# Cargador_RasPi3HAT_CamSlot_v1_2.net
KiCad netlist of a schematic drawn in EAGLE
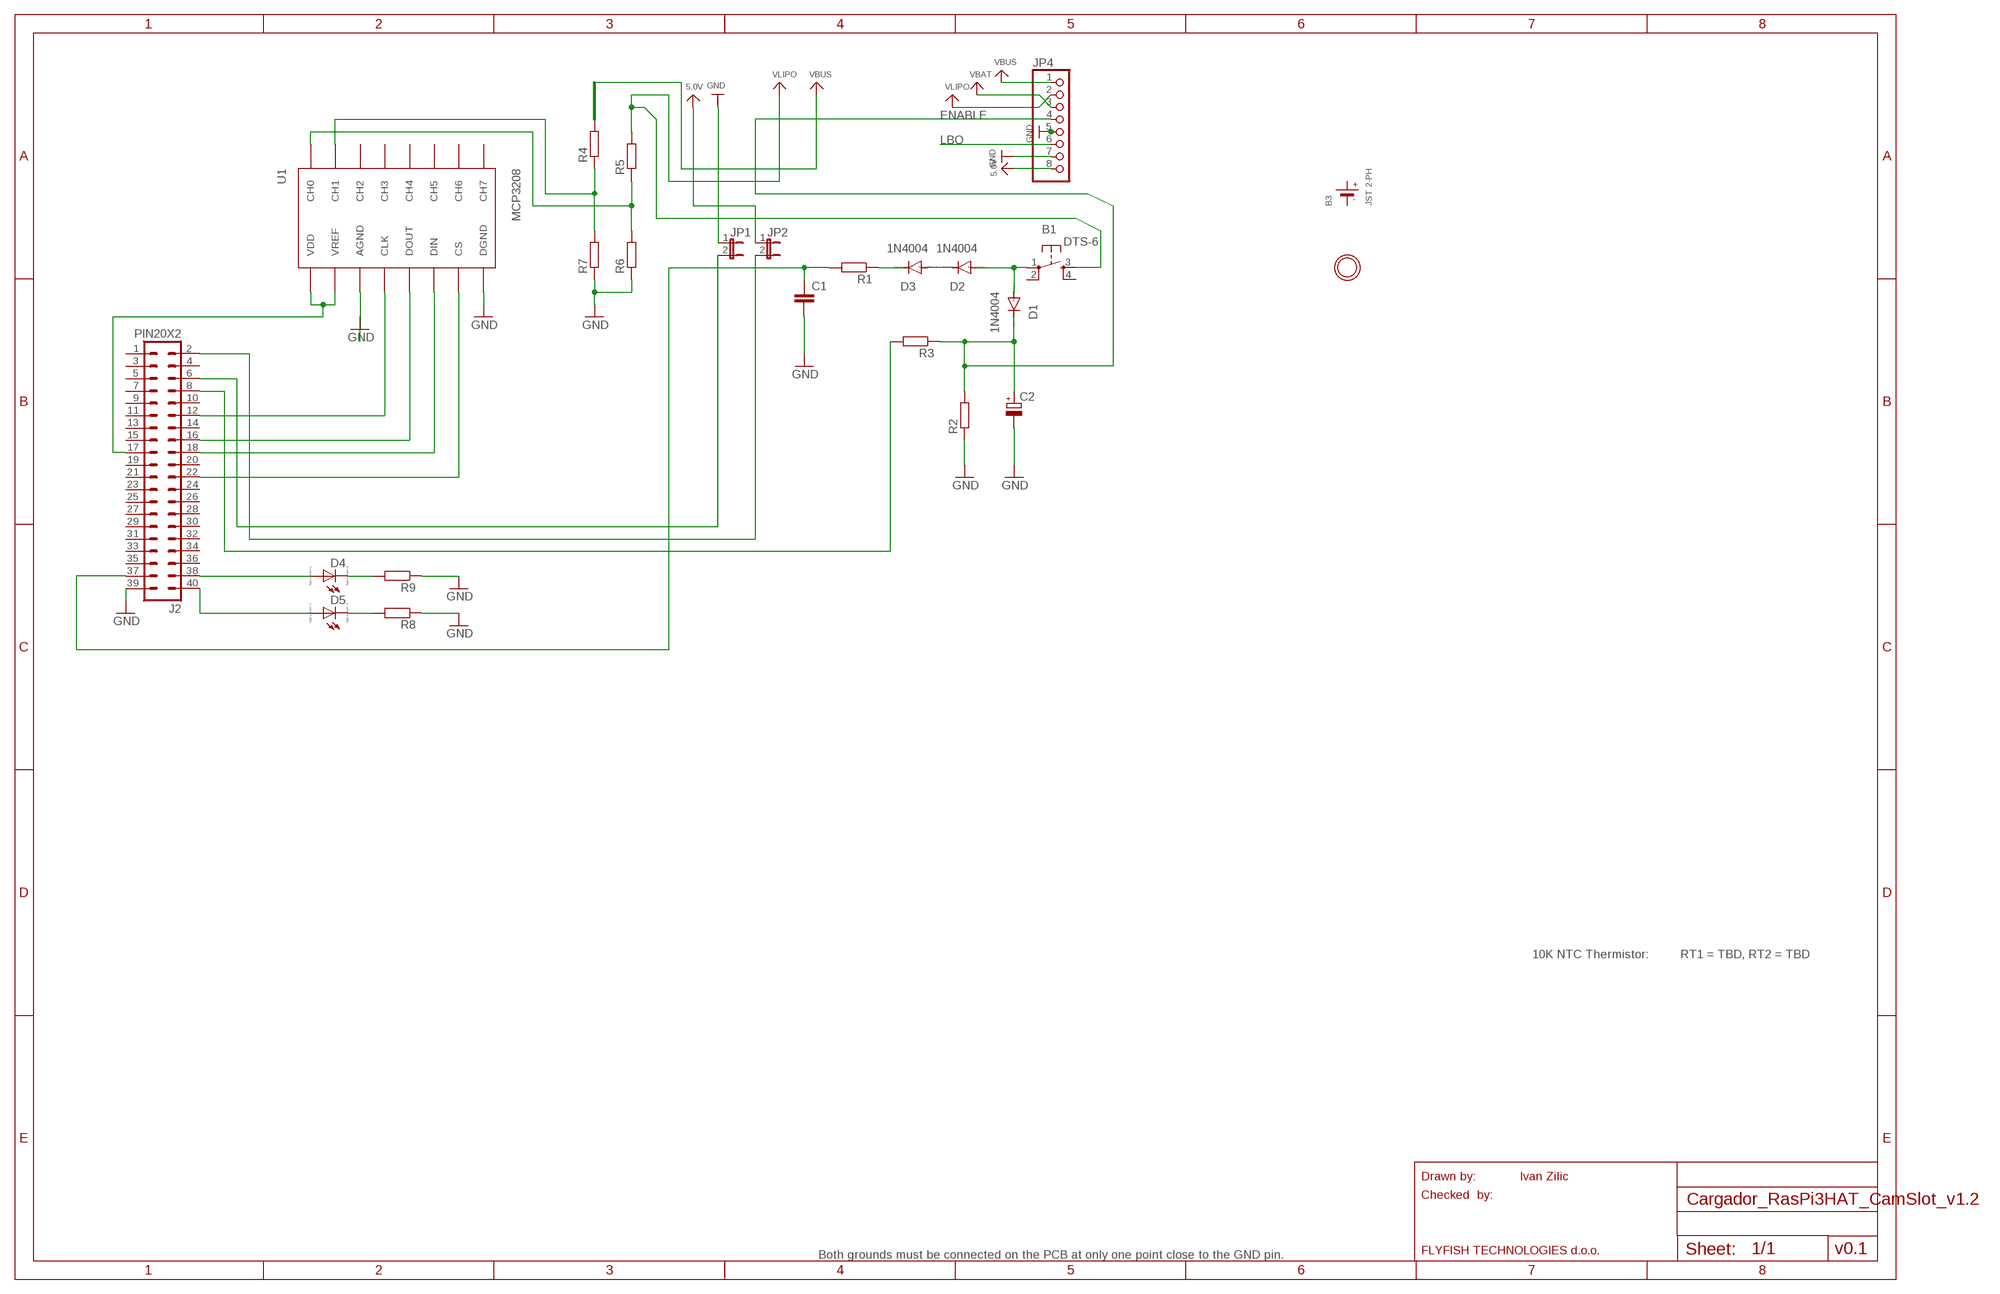
[diagram p0: schematic, sheet 1]

(export (version "E")
  (design (tool "Eeschema 10.0.6"))
  (components
    (comp (ref "B1")
      (value "DTS-6")
      (footprint "eagle-import:DTS-6")
      (libsource (lib "eagle-import") (part "DTS-6"))
    )
    (comp (ref "B3")
      (value "JST 2-PH")
      (footprint "eagle-import:JSTPH2")
      (libsource (lib "eagle-import") (part "BATTERY"))
    )
    (comp (ref "C1")
      (value "C2.5/2")
      (footprint "eagle-import:C2.5-2")
      (libsource (lib "eagle-import") (part "C2.5/2"))
    )
    (comp (ref "C2")
      (value "CPOL-EUE5-4")
      (footprint "eagle-import:E5-4")
      (libsource (lib "eagle-import") (part "CPOL-EUE5-4"))
    )
    (comp (ref "D1")
      (value "1N4004")
      (footprint "eagle-import:DO41-10")
      (libsource (lib "eagle-import") (part "1N4004"))
    )
    (comp (ref "D2")
      (value "1N4004")
      (footprint "eagle-import:DO41-10")
      (libsource (lib "eagle-import") (part "1N4004"))
    )
    (comp (ref "D3")
      (value "1N4004")
      (footprint "eagle-import:DO41-10")
      (libsource (lib "eagle-import") (part "1N4004"))
    )
    (comp (ref "D4")
      (value "LED_ELD260")
      (footprint "eagle-import:LED_LD260")
      (libsource (lib "eagle-import") (part "LED_ELD260"))
    )
    (comp (ref "D5")
      (value "LED_ELD260")
      (footprint "eagle-import:LED_LD260")
      (libsource (lib "eagle-import") (part "LED_ELD260"))
    )
    (comp (ref "J2")
      (value "PIN20X2")
      (footprint "eagle-import:PIN_20X2")
      (libsource (lib "eagle-import") (part "PIN20X2"))
    )
    (comp (ref "JP1")
      (value "JP1E")
      (footprint "eagle-import:JP1")
      (libsource (lib "eagle-import") (part "JP1E"))
    )
    (comp (ref "JP2")
      (value "JP1E")
      (footprint "eagle-import:JP1")
      (libsource (lib "eagle-import") (part "JP1E"))
    )
    (comp (ref "JP4")
      (value "HEADER-1X8")
      (footprint "eagle-import:1X08_OVAL")
      (libsource (lib "eagle-import") (part "HEADER-1X8"))
    )
    (comp (ref "R1")
      (value "R-EU_0207/10")
      (footprint "eagle-import:0207_10")
      (libsource (lib "eagle-import") (part "R-EU_0207/10"))
    )
    (comp (ref "R2")
      (value "R-EU_0207/10")
      (footprint "eagle-import:0207_10")
      (libsource (lib "eagle-import") (part "R-EU_0207/10"))
    )
    (comp (ref "R3")
      (value "R-EU_0207/10")
      (footprint "eagle-import:0207_10")
      (libsource (lib "eagle-import") (part "R-EU_0207/10"))
    )
    (comp (ref "R4")
      (value "R-EU_0207/10")
      (footprint "eagle-import:0207_10")
      (libsource (lib "eagle-import") (part "R-EU_0207/10"))
    )
    (comp (ref "R5")
      (value "R-EU_0207/10")
      (footprint "eagle-import:0207_10")
      (libsource (lib "eagle-import") (part "R-EU_0207/10"))
    )
    (comp (ref "R6")
      (value "R-EU_0207/10")
      (footprint "eagle-import:0207_10")
      (libsource (lib "eagle-import") (part "R-EU_0207/10"))
    )
    (comp (ref "R7")
      (value "R-EU_0207/10")
      (footprint "eagle-import:0207_10")
      (libsource (lib "eagle-import") (part "R-EU_0207/10"))
    )
    (comp (ref "R8")
      (value "R-EU_0207/10")
      (footprint "eagle-import:0207_10")
      (libsource (lib "eagle-import") (part "R-EU_0207/10"))
    )
    (comp (ref "R9")
      (value "R-EU_0207/10")
      (footprint "eagle-import:0207_10")
      (libsource (lib "eagle-import") (part "R-EU_0207/10"))
    )
    (comp (ref "U$5")
      (value "MOUNTINGHOLE2.5")
      (footprint "eagle-import:MOUNTINGHOLE_2.5_PLATED")
      (libsource (lib "eagle-import") (part "MOUNTINGHOLE2.5"))
    )
    (comp (ref "U1")
      (value "MCP3208")
      (footprint "eagle-import:DIL16")
      (libsource (lib "eagle-import") (part "MCP3208"))
    )
  )
  (nets
    (net (code "1") (name "/ENABLE") (class "Default")
      (node (ref "C2") (pin "+") (pinfunction "+_+") (pintype "passive"))
      (node (ref "D1") (pin "C") (pinfunction "C_C") (pintype "passive"))
      (node (ref "JP4") (pin "4") (pinfunction "4_4") (pintype "passive"))
      (node (ref "R2") (pin "2") (pinfunction "2_2") (pintype "passive"))
      (node (ref "R3") (pin "1") (pinfunction "1_1") (pintype "passive"))
    )
    (net (code "2") (name "/LBO") (class "Default")
      (node (ref "JP4") (pin "6") (pinfunction "6_6") (pintype "passive"))
    )
    (net (code "3") (name "5.0V") (class "Default")
      (node (ref "JP2") (pin "1") (pinfunction "1_1") (pintype "passive"))
      (node (ref "JP4") (pin "8") (pinfunction "8_8") (pintype "passive"))
    )
    (net (code "4") (name "GND") (class "Default")
      (node (ref "C1") (pin "2") (pinfunction "2_2") (pintype "passive"))
      (node (ref "C2") (pin "-") (pinfunction "-_-") (pintype "passive"))
      (node (ref "J2") (pin "39") (pinfunction "39_39") (pintype "passive"))
      (node (ref "JP1") (pin "1") (pinfunction "1_1") (pintype "passive"))
      (node (ref "JP4") (pin "5") (pinfunction "5_5") (pintype "passive"))
      (node (ref "JP4") (pin "7") (pinfunction "7_7") (pintype "passive"))
      (node (ref "R2") (pin "1") (pinfunction "1_1") (pintype "passive"))
      (node (ref "R6") (pin "1") (pinfunction "1_1") (pintype "passive"))
      (node (ref "R7") (pin "1") (pinfunction "1_1") (pintype "passive"))
      (node (ref "R8") (pin "1") (pinfunction "1_1") (pintype "passive"))
      (node (ref "R9") (pin "1") (pinfunction "1_1") (pintype "passive"))
      (node (ref "U1") (pin "AGND") (pinfunction "AGND_AGND") (pintype "power_in"))
      (node (ref "U1") (pin "DGND") (pinfunction "DGND_DGND") (pintype "power_in"))
    )
    (net (code "5") (name "Net-(B1-Pad1)") (class "Default")
      (node (ref "B1") (pin "1") (pinfunction "1_1") (pintype "passive"))
      (node (ref "D1") (pin "A") (pinfunction "A_A") (pintype "passive"))
      (node (ref "D2") (pin "A") (pinfunction "A_A") (pintype "passive"))
    )
    (net (code "6") (name "Net-(C1-Pad1)") (class "Default")
      (node (ref "C1") (pin "1") (pinfunction "1_1") (pintype "passive"))
      (node (ref "J2") (pin "37") (pinfunction "37_37") (pintype "passive"))
      (node (ref "R1") (pin "2") (pinfunction "2_2") (pintype "passive"))
    )
    (net (code "7") (name "Net-(D2-PadC)") (class "Default")
      (node (ref "D2") (pin "C") (pinfunction "C_C") (pintype "passive"))
      (node (ref "D3") (pin "A") (pinfunction "A_A") (pintype "passive"))
    )
    (net (code "8") (name "Net-(D3-PadC)") (class "Default")
      (node (ref "D3") (pin "C") (pinfunction "C_C") (pintype "passive"))
      (node (ref "R1") (pin "1") (pinfunction "1_1") (pintype "passive"))
    )
    (net (code "9") (name "Net-(D4-C)") (class "Default")
      (node (ref "D4") (pin "K") (pinfunction "C_K") (pintype "passive"))
      (node (ref "R9") (pin "2") (pinfunction "2_2") (pintype "passive"))
    )
    (net (code "10") (name "Net-(D4-PadA)") (class "Default")
      (node (ref "D4") (pin "A") (pinfunction "A_A") (pintype "passive"))
      (node (ref "J2") (pin "38") (pinfunction "38_38") (pintype "passive"))
    )
    (net (code "11") (name "Net-(D5-C)") (class "Default")
      (node (ref "D5") (pin "K") (pinfunction "C_K") (pintype "passive"))
      (node (ref "R8") (pin "2") (pinfunction "2_2") (pintype "passive"))
    )
    (net (code "12") (name "Net-(D5-PadA)") (class "Default")
      (node (ref "D5") (pin "A") (pinfunction "A_A") (pintype "passive"))
      (node (ref "J2") (pin "40") (pinfunction "40_40") (pintype "passive"))
    )
    (net (code "13") (name "Net-(J2-Pad2)") (class "Default")
      (node (ref "J2") (pin "2") (pinfunction "2_2") (pintype "passive"))
      (node (ref "JP2") (pin "2") (pinfunction "2_2") (pintype "passive"))
    )
    (net (code "14") (name "Net-(J2-Pad6)") (class "Default")
      (node (ref "J2") (pin "6") (pinfunction "6_6") (pintype "passive"))
      (node (ref "JP1") (pin "2") (pinfunction "2_2") (pintype "passive"))
    )
    (net (code "15") (name "Net-(J2-Pad8)") (class "Default")
      (node (ref "J2") (pin "8") (pinfunction "8_8") (pintype "passive"))
      (node (ref "R3") (pin "2") (pinfunction "2_2") (pintype "passive"))
    )
    (net (code "16") (name "Net-(J2-Pad12)") (class "Default")
      (node (ref "J2") (pin "12") (pinfunction "12_12") (pintype "passive"))
      (node (ref "U1") (pin "CLK") (pinfunction "CLK_CLK") (pintype "input"))
    )
    (net (code "17") (name "Net-(J2-Pad16)") (class "Default")
      (node (ref "J2") (pin "16") (pinfunction "16_16") (pintype "passive"))
      (node (ref "U1") (pin "DOUT") (pinfunction "DOUT_DOUT") (pintype "output"))
    )
    (net (code "18") (name "Net-(J2-Pad17)") (class "Default")
      (node (ref "J2") (pin "17") (pinfunction "17_17") (pintype "passive"))
      (node (ref "U1") (pin "VDD") (pinfunction "VDD_VDD") (pintype "power_in"))
      (node (ref "U1") (pin "VREF") (pinfunction "VREF_VREF") (pintype "input"))
    )
    (net (code "19") (name "Net-(J2-Pad18)") (class "Default")
      (node (ref "J2") (pin "18") (pinfunction "18_18") (pintype "passive"))
      (node (ref "U1") (pin "DIN") (pinfunction "DIN_DIN") (pintype "input"))
    )
    (net (code "20") (name "Net-(J2-Pad22)") (class "Default")
      (node (ref "J2") (pin "22") (pinfunction "22_22") (pintype "passive"))
      (node (ref "U1") (pin "CS") (pinfunction "CS_CS") (pintype "input"))
    )
    (net (code "21") (name "Net-(R4-Pad1)") (class "Default")
      (node (ref "R4") (pin "1") (pinfunction "1_1") (pintype "passive"))
      (node (ref "R7") (pin "2") (pinfunction "2_2") (pintype "passive"))
      (node (ref "U1") (pin "CH1") (pinfunction "CH1_CH1") (pintype "input"))
    )
    (net (code "22") (name "Net-(R5-Pad1)") (class "Default")
      (node (ref "R5") (pin "1") (pinfunction "1_1") (pintype "passive"))
      (node (ref "R6") (pin "2") (pinfunction "2_2") (pintype "passive"))
      (node (ref "U1") (pin "CH0") (pinfunction "CH0_CH0") (pintype "input"))
    )
    (net (code "23") (name "VBAT") (class "Default")
      (node (ref "JP4") (pin "3") (pinfunction "3_3") (pintype "passive"))
    )
    (net (code "24") (name "VBUS") (class "Default")
      (node (ref "JP4") (pin "1") (pinfunction "1_1") (pintype "passive"))
      (node (ref "R4") (pin "2") (pinfunction "2_2") (pintype "passive"))
    )
    (net (code "25") (name "VLIPO") (class "Default")
      (node (ref "B1") (pin "3") (pinfunction "3_3") (pintype "passive"))
      (node (ref "JP4") (pin "2") (pinfunction "2_2") (pintype "passive"))
      (node (ref "R5") (pin "2") (pinfunction "2_2") (pintype "passive"))
    )
    (net (code "26") (name "unconnected-(B1-Pad2)") (class "Default")
      (node (ref "B1") (pin "2") (pinfunction "2_2") (pintype "passive"))
    )
    (net (code "27") (name "unconnected-(B1-Pad4)") (class "Default")
      (node (ref "B1") (pin "4") (pinfunction "4_4") (pintype "passive"))
    )
    (net (code "28") (name "unconnected-(B3-+-Pad2)") (class "Default")
      (node (ref "B3") (pin "2") (pinfunction "+_2") (pintype "passive"))
    )
    (net (code "29") (name "unconnected-(B3---Pad1)") (class "Default")
      (node (ref "B3") (pin "1") (pinfunction "-_1") (pintype "passive"))
    )
    (net (code "30") (name "unconnected-(J2-Pad1)") (class "Default")
      (node (ref "J2") (pin "1") (pinfunction "1_1") (pintype "passive"))
    )
    (net (code "31") (name "unconnected-(J2-Pad3)") (class "Default")
      (node (ref "J2") (pin "3") (pinfunction "3_3") (pintype "passive"))
    )
    (net (code "32") (name "unconnected-(J2-Pad4)") (class "Default")
      (node (ref "J2") (pin "4") (pinfunction "4_4") (pintype "passive"))
    )
    (net (code "33") (name "unconnected-(J2-Pad5)") (class "Default")
      (node (ref "J2") (pin "5") (pinfunction "5_5") (pintype "passive"))
    )
    (net (code "34") (name "unconnected-(J2-Pad7)") (class "Default")
      (node (ref "J2") (pin "7") (pinfunction "7_7") (pintype "passive"))
    )
    (net (code "35") (name "unconnected-(J2-Pad9)") (class "Default")
      (node (ref "J2") (pin "9") (pinfunction "9_9") (pintype "passive"))
    )
    (net (code "36") (name "unconnected-(J2-Pad10)") (class "Default")
      (node (ref "J2") (pin "10") (pinfunction "10_10") (pintype "passive"))
    )
    (net (code "37") (name "unconnected-(J2-Pad11)") (class "Default")
      (node (ref "J2") (pin "11") (pinfunction "11_11") (pintype "passive"))
    )
    (net (code "38") (name "unconnected-(J2-Pad13)") (class "Default")
      (node (ref "J2") (pin "13") (pinfunction "13_13") (pintype "passive"))
    )
    (net (code "39") (name "unconnected-(J2-Pad14)") (class "Default")
      (node (ref "J2") (pin "14") (pinfunction "14_14") (pintype "passive"))
    )
    (net (code "40") (name "unconnected-(J2-Pad15)") (class "Default")
      (node (ref "J2") (pin "15") (pinfunction "15_15") (pintype "passive"))
    )
    (net (code "41") (name "unconnected-(J2-Pad19)") (class "Default")
      (node (ref "J2") (pin "19") (pinfunction "19_19") (pintype "passive"))
    )
    (net (code "42") (name "unconnected-(J2-Pad20)") (class "Default")
      (node (ref "J2") (pin "20") (pinfunction "20_20") (pintype "passive"))
    )
    (net (code "43") (name "unconnected-(J2-Pad21)") (class "Default")
      (node (ref "J2") (pin "21") (pinfunction "21_21") (pintype "passive"))
    )
    (net (code "44") (name "unconnected-(J2-Pad23)") (class "Default")
      (node (ref "J2") (pin "23") (pinfunction "23_23") (pintype "passive"))
    )
    (net (code "45") (name "unconnected-(J2-Pad24)") (class "Default")
      (node (ref "J2") (pin "24") (pinfunction "24_24") (pintype "passive"))
    )
    (net (code "46") (name "unconnected-(J2-Pad25)") (class "Default")
      (node (ref "J2") (pin "25") (pinfunction "25_25") (pintype "passive"))
    )
    (net (code "47") (name "unconnected-(J2-Pad26)") (class "Default")
      (node (ref "J2") (pin "26") (pinfunction "26_26") (pintype "passive"))
    )
    (net (code "48") (name "unconnected-(J2-Pad27)") (class "Default")
      (node (ref "J2") (pin "27") (pinfunction "27_27") (pintype "passive"))
    )
    (net (code "49") (name "unconnected-(J2-Pad28)") (class "Default")
      (node (ref "J2") (pin "28") (pinfunction "28_28") (pintype "passive"))
    )
    (net (code "50") (name "unconnected-(J2-Pad29)") (class "Default")
      (node (ref "J2") (pin "29") (pinfunction "29_29") (pintype "passive"))
    )
    (net (code "51") (name "unconnected-(J2-Pad30)") (class "Default")
      (node (ref "J2") (pin "30") (pinfunction "30_30") (pintype "passive"))
    )
    (net (code "52") (name "unconnected-(J2-Pad31)") (class "Default")
      (node (ref "J2") (pin "31") (pinfunction "31_31") (pintype "passive"))
    )
    (net (code "53") (name "unconnected-(J2-Pad32)") (class "Default")
      (node (ref "J2") (pin "32") (pinfunction "32_32") (pintype "passive"))
    )
    (net (code "54") (name "unconnected-(J2-Pad33)") (class "Default")
      (node (ref "J2") (pin "33") (pinfunction "33_33") (pintype "passive"))
    )
    (net (code "55") (name "unconnected-(J2-Pad34)") (class "Default")
      (node (ref "J2") (pin "34") (pinfunction "34_34") (pintype "passive"))
    )
    (net (code "56") (name "unconnected-(J2-Pad35)") (class "Default")
      (node (ref "J2") (pin "35") (pinfunction "35_35") (pintype "passive"))
    )
    (net (code "57") (name "unconnected-(J2-Pad36)") (class "Default")
      (node (ref "J2") (pin "36") (pinfunction "36_36") (pintype "passive"))
    )
    (net (code "58") (name "unconnected-(U1-PadCH2)") (class "Default")
      (node (ref "U1") (pin "CH2") (pinfunction "CH2_CH2") (pintype "input"))
    )
    (net (code "59") (name "unconnected-(U1-PadCH3)") (class "Default")
      (node (ref "U1") (pin "CH3") (pinfunction "CH3_CH3") (pintype "input"))
    )
    (net (code "60") (name "unconnected-(U1-PadCH4)") (class "Default")
      (node (ref "U1") (pin "CH4") (pinfunction "CH4_CH4") (pintype "input"))
    )
    (net (code "61") (name "unconnected-(U1-PadCH5)") (class "Default")
      (node (ref "U1") (pin "CH5") (pinfunction "CH5_CH5") (pintype "input"))
    )
    (net (code "62") (name "unconnected-(U1-PadCH6)") (class "Default")
      (node (ref "U1") (pin "CH6") (pinfunction "CH6_CH6") (pintype "input"))
    )
    (net (code "63") (name "unconnected-(U1-PadCH7)") (class "Default")
      (node (ref "U1") (pin "CH7") (pinfunction "CH7_CH7") (pintype "input"))
    )
  )
)
